# tapometer.net
KiCad netlist of a schematic drawn in EAGLE
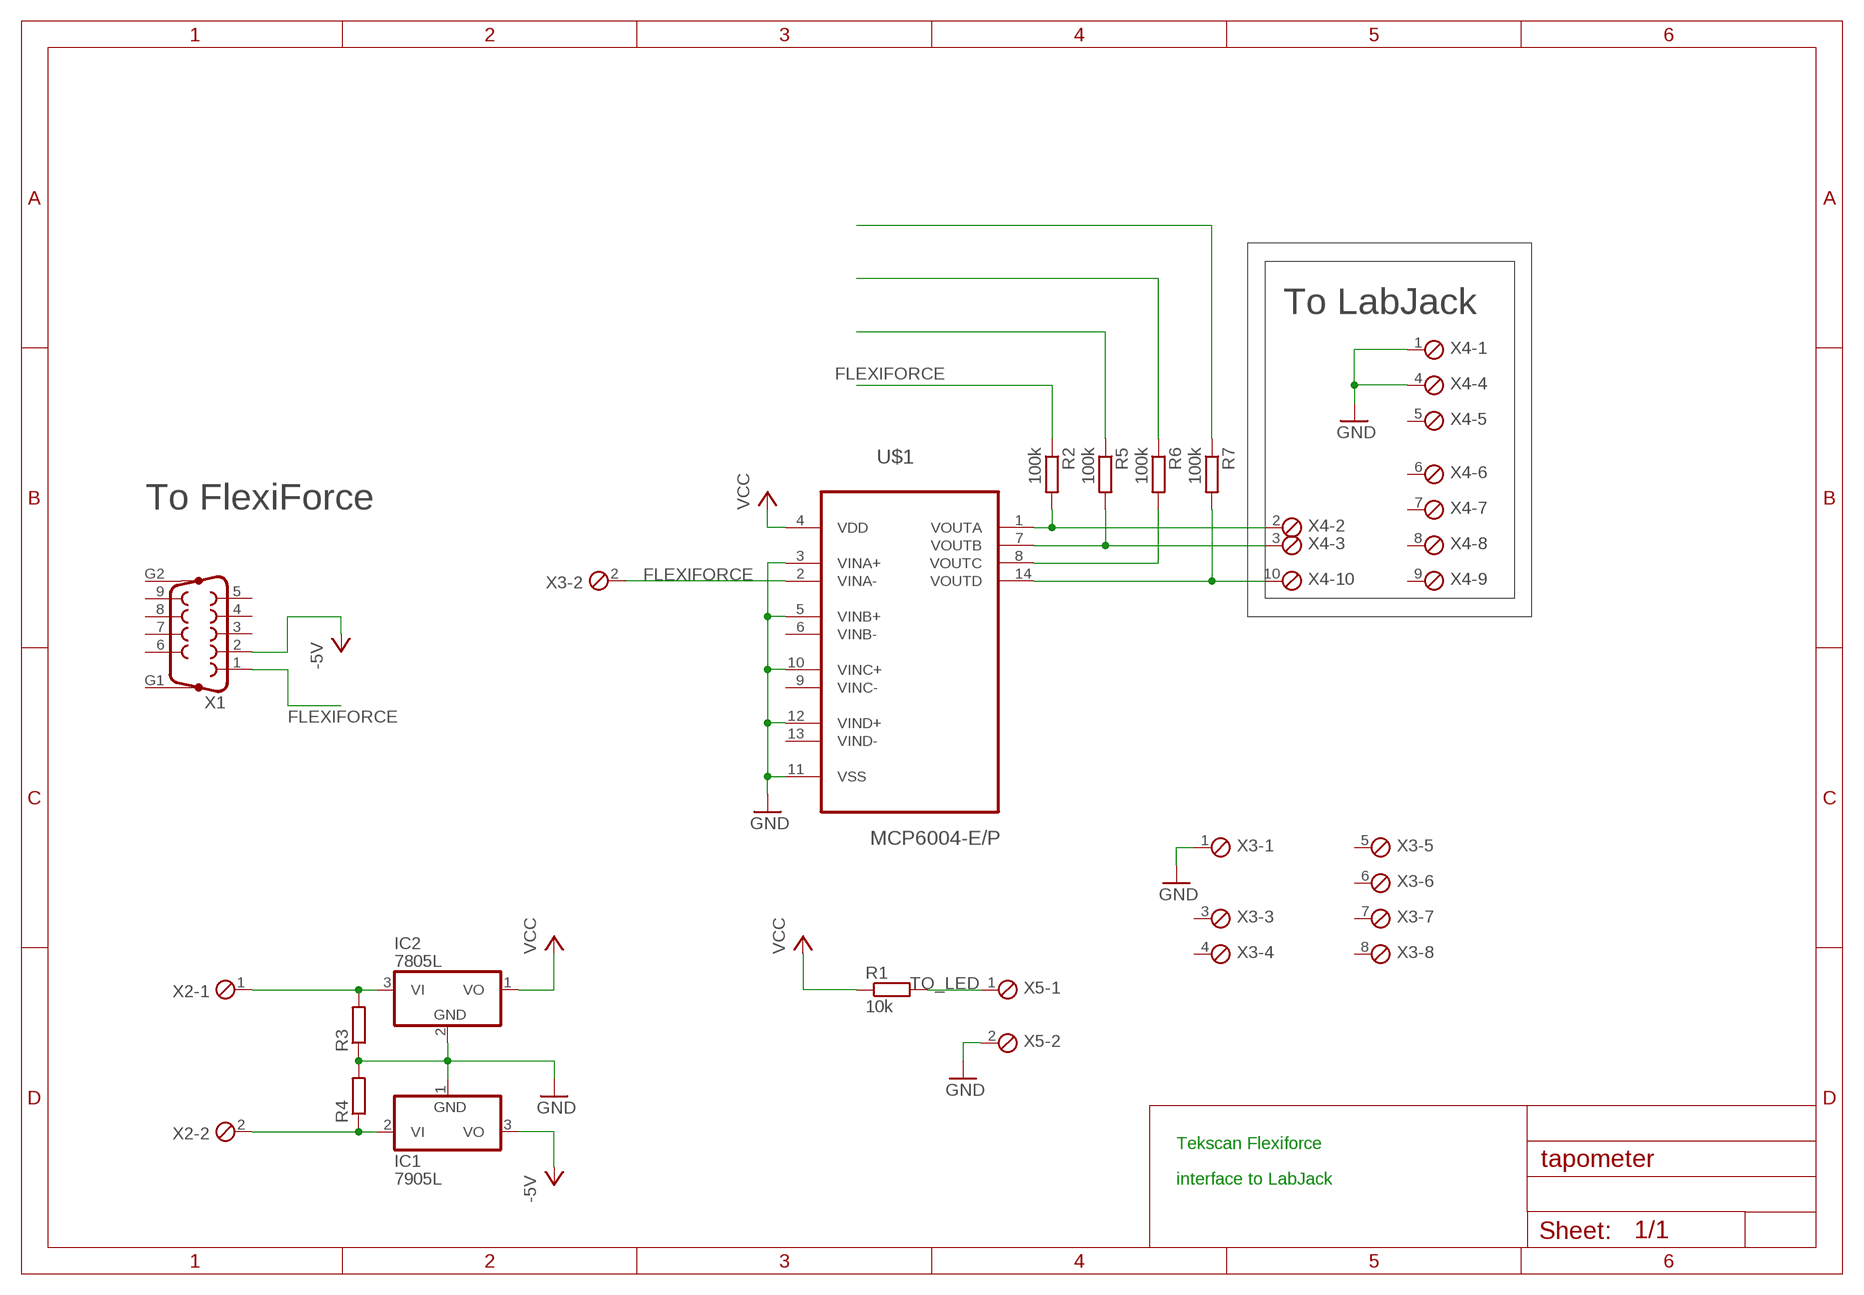
[diagram p0: schematic, sheet 1]

(export (version "E")
  (design (tool "Eeschema 10.0.6"))
  (components
    (comp (ref "IC1")
      (value "7905L")
      (footprint "eagle-import:TO92")
      (libsource (lib "eagle-import") (part "79L05"))
    )
    (comp (ref "IC2")
      (value "7805L")
      (footprint "eagle-import:TO92")
      (libsource (lib "eagle-import") (part "78L05"))
    )
    (comp (ref "R1")
      (value "10k")
      (footprint "eagle-import:0207_10")
      (libsource (lib "eagle-import") (part "R-EU_0207/10"))
    )
    (comp (ref "R2")
      (value "100k")
      (footprint "eagle-import:0207_10")
      (libsource (lib "eagle-import") (part "R-EU_0207/10"))
    )
    (comp (ref "R3")
      (value "R-EU_0207/10")
      (footprint "eagle-import:0207_10")
      (libsource (lib "eagle-import") (part "R-EU_0207/10"))
    )
    (comp (ref "R4")
      (value "R-EU_0207/10")
      (footprint "eagle-import:0207_10")
      (libsource (lib "eagle-import") (part "R-EU_0207/10"))
    )
    (comp (ref "R5")
      (value "100k")
      (footprint "eagle-import:0207_10")
      (libsource (lib "eagle-import") (part "R-EU_0207/10"))
    )
    (comp (ref "R6")
      (value "100k")
      (footprint "eagle-import:0207_10")
      (libsource (lib "eagle-import") (part "R-EU_0207/10"))
    )
    (comp (ref "R7")
      (value "100k")
      (footprint "eagle-import:0207_10")
      (libsource (lib "eagle-import") (part "R-EU_0207/10"))
    )
    (comp (ref "U$1")
      (value "MCP6004-E/P")
      (footprint "eagle-import:DIP254P762X533-14")
      (libsource (lib "eagle-import") (part "MCP6004-E/P"))
    )
    (comp (ref "X1")
      (value "F09HP")
      (footprint "eagle-import:F09HP")
      (libsource (lib "eagle-import") (part "F09HP"))
    )
    (comp (ref "X2")
      (value "MPT2")
      (footprint "eagle-import:2POL254")
      (libsource (lib "eagle-import") (part "MPT2"))
    )
    (comp (ref "X3")
      (value "MPT8")
      (footprint "eagle-import:8POL254")
      (libsource (lib "eagle-import") (part "MPT8"))
    )
    (comp (ref "X4")
      (value "MPT10")
      (footprint "eagle-import:10POL254")
      (libsource (lib "eagle-import") (part "MPT10"))
    )
    (comp (ref "X5")
      (value "MPT2")
      (footprint "eagle-import:2POL254")
      (libsource (lib "eagle-import") (part "MPT2"))
    )
  )
  (nets
    (net (code "1") (name "-5V") (class "Default")
      (node (ref "IC1") (pin "3") (pinfunction "VO_3") (pintype "passive"))
      (node (ref "X1") (pin "2") (pinfunction "2_2") (pintype "passive"))
    )
    (net (code "2") (name "/FLEXIFORCE") (class "Default")
      (node (ref "R2") (pin "1") (pinfunction "1_1") (pintype "passive"))
      (node (ref "U$1") (pin "2") (pinfunction "VINA-_2") (pintype "input"))
      (node (ref "X1") (pin "1") (pinfunction "1_1") (pintype "passive"))
      (node (ref "X3") (pin "2") (pinfunction "1_2") (pintype "passive"))
    )
    (net (code "3") (name "/TO_LED") (class "Default")
      (node (ref "R1") (pin "2") (pinfunction "2_2") (pintype "passive"))
      (node (ref "X5") (pin "1") (pinfunction "1_1") (pintype "passive"))
    )
    (net (code "4") (name "GND") (class "Default")
      (node (ref "IC1") (pin "1") (pinfunction "GND_1") (pintype "passive"))
      (node (ref "IC2") (pin "2") (pinfunction "GND_2") (pintype "passive"))
      (node (ref "R3") (pin "1") (pinfunction "1_1") (pintype "passive"))
      (node (ref "R4") (pin "2") (pinfunction "2_2") (pintype "passive"))
      (node (ref "U$1") (pin "10") (pinfunction "VINC+_10") (pintype "input"))
      (node (ref "U$1") (pin "11") (pinfunction "VSS_11") (pintype "power_in"))
      (node (ref "U$1") (pin "12") (pinfunction "VIND+_12") (pintype "input"))
      (node (ref "U$1") (pin "3") (pinfunction "VINA+_3") (pintype "input"))
      (node (ref "U$1") (pin "5") (pinfunction "VINB+_5") (pintype "input"))
      (node (ref "X3") (pin "1") (pinfunction "1_1") (pintype "passive"))
      (node (ref "X4") (pin "1") (pinfunction "1_1") (pintype "passive"))
      (node (ref "X4") (pin "4") (pinfunction "1_4") (pintype "passive"))
      (node (ref "X5") (pin "2") (pinfunction "1_2") (pintype "passive"))
    )
    (net (code "5") (name "Net-(IC1-VI)") (class "Default")
      (node (ref "IC1") (pin "2") (pinfunction "VI_2") (pintype "input"))
      (node (ref "R4") (pin "1") (pinfunction "1_1") (pintype "passive"))
      (node (ref "X2") (pin "2") (pinfunction "1_2") (pintype "passive"))
    )
    (net (code "6") (name "Net-(IC2-VI)") (class "Default")
      (node (ref "IC2") (pin "3") (pinfunction "VI_3") (pintype "input"))
      (node (ref "R3") (pin "2") (pinfunction "2_2") (pintype "passive"))
      (node (ref "X2") (pin "1") (pinfunction "1_1") (pintype "passive"))
    )
    (net (code "7") (name "Net-(U$1-VOUTA)") (class "Default")
      (node (ref "R2") (pin "2") (pinfunction "2_2") (pintype "passive"))
      (node (ref "U$1") (pin "1") (pinfunction "VOUTA_1") (pintype "output"))
      (node (ref "X4") (pin "2") (pinfunction "1_2") (pintype "passive"))
    )
    (net (code "8") (name "Net-(U$1-VOUTB)") (class "Default")
      (node (ref "R5") (pin "2") (pinfunction "2_2") (pintype "passive"))
      (node (ref "U$1") (pin "7") (pinfunction "VOUTB_7") (pintype "output"))
      (node (ref "X4") (pin "3") (pinfunction "1_3") (pintype "passive"))
    )
    (net (code "9") (name "Net-(U$1-VOUTC)") (class "Default")
      (node (ref "R6") (pin "2") (pinfunction "2_2") (pintype "passive"))
      (node (ref "U$1") (pin "8") (pinfunction "VOUTC_8") (pintype "output"))
    )
    (net (code "10") (name "Net-(U$1-VOUTD)") (class "Default")
      (node (ref "R7") (pin "2") (pinfunction "2_2") (pintype "passive"))
      (node (ref "U$1") (pin "14") (pinfunction "VOUTD_14") (pintype "output"))
      (node (ref "X4") (pin "10") (pinfunction "1_10") (pintype "passive"))
    )
    (net (code "11") (name "VCC") (class "Default")
      (node (ref "IC2") (pin "1") (pinfunction "VO_1") (pintype "passive"))
      (node (ref "R1") (pin "1") (pinfunction "1_1") (pintype "passive"))
      (node (ref "U$1") (pin "4") (pinfunction "VDD_4") (pintype "power_in"))
    )
    (net (code "12") (name "unconnected-(R5-Pad1)") (class "Default")
      (node (ref "R5") (pin "1") (pinfunction "1_1") (pintype "passive"))
    )
    (net (code "13") (name "unconnected-(R6-Pad1)") (class "Default")
      (node (ref "R6") (pin "1") (pinfunction "1_1") (pintype "passive"))
    )
    (net (code "14") (name "unconnected-(R7-Pad1)") (class "Default")
      (node (ref "R7") (pin "1") (pinfunction "1_1") (pintype "passive"))
    )
    (net (code "15") (name "unconnected-(U$1-VINB--Pad6)") (class "Default")
      (node (ref "U$1") (pin "6") (pinfunction "VINB-_6") (pintype "input"))
    )
    (net (code "16") (name "unconnected-(U$1-VINC--Pad9)") (class "Default")
      (node (ref "U$1") (pin "9") (pinfunction "VINC-_9") (pintype "input"))
    )
    (net (code "17") (name "unconnected-(U$1-VIND--Pad13)") (class "Default")
      (node (ref "U$1") (pin "13") (pinfunction "VIND-_13") (pintype "input"))
    )
    (net (code "18") (name "unconnected-(X1-Pad3)") (class "Default")
      (node (ref "X1") (pin "3") (pinfunction "3_3") (pintype "passive"))
    )
    (net (code "19") (name "unconnected-(X1-Pad4)") (class "Default")
      (node (ref "X1") (pin "4") (pinfunction "4_4") (pintype "passive"))
    )
    (net (code "20") (name "unconnected-(X1-Pad5)") (class "Default")
      (node (ref "X1") (pin "5") (pinfunction "5_5") (pintype "passive"))
    )
    (net (code "21") (name "unconnected-(X1-Pad6)") (class "Default")
      (node (ref "X1") (pin "6") (pinfunction "6_6") (pintype "passive"))
    )
    (net (code "22") (name "unconnected-(X1-Pad7)") (class "Default")
      (node (ref "X1") (pin "7") (pinfunction "7_7") (pintype "passive"))
    )
    (net (code "23") (name "unconnected-(X1-Pad8)") (class "Default")
      (node (ref "X1") (pin "8") (pinfunction "8_8") (pintype "passive"))
    )
    (net (code "24") (name "unconnected-(X1-Pad9)") (class "Default")
      (node (ref "X1") (pin "9") (pinfunction "9_9") (pintype "passive"))
    )
    (net (code "25") (name "unconnected-(X1-PadG1)") (class "Default")
      (node (ref "X1") (pin "G1") (pinfunction "G1_G1") (pintype "passive"))
    )
    (net (code "26") (name "unconnected-(X1-PadG2)") (class "Default")
      (node (ref "X1") (pin "G2") (pinfunction "G2_G2") (pintype "passive"))
    )
    (net (code "27") (name "unconnected-(X3C-1-Pad3)") (class "Default")
      (node (ref "X3") (pin "3") (pinfunction "1_3") (pintype "passive"))
    )
    (net (code "28") (name "unconnected-(X3D-1-Pad4)") (class "Default")
      (node (ref "X3") (pin "4") (pinfunction "1_4") (pintype "passive"))
    )
    (net (code "29") (name "unconnected-(X3E-1-Pad5)") (class "Default")
      (node (ref "X3") (pin "5") (pinfunction "1_5") (pintype "passive"))
    )
    (net (code "30") (name "unconnected-(X3F-1-Pad6)") (class "Default")
      (node (ref "X3") (pin "6") (pinfunction "1_6") (pintype "passive"))
    )
    (net (code "31") (name "unconnected-(X3G-1-Pad7)") (class "Default")
      (node (ref "X3") (pin "7") (pinfunction "1_7") (pintype "passive"))
    )
    (net (code "32") (name "unconnected-(X3H-1-Pad8)") (class "Default")
      (node (ref "X3") (pin "8") (pinfunction "1_8") (pintype "passive"))
    )
    (net (code "33") (name "unconnected-(X4F-1-Pad5)") (class "Default")
      (node (ref "X4") (pin "5") (pinfunction "1_5") (pintype "passive"))
    )
    (net (code "34") (name "unconnected-(X4G-1-Pad6)") (class "Default")
      (node (ref "X4") (pin "6") (pinfunction "1_6") (pintype "passive"))
    )
    (net (code "35") (name "unconnected-(X4H-1-Pad7)") (class "Default")
      (node (ref "X4") (pin "7") (pinfunction "1_7") (pintype "passive"))
    )
    (net (code "36") (name "unconnected-(X4I-1-Pad8)") (class "Default")
      (node (ref "X4") (pin "8") (pinfunction "1_8") (pintype "passive"))
    )
    (net (code "37") (name "unconnected-(X4J-1-Pad9)") (class "Default")
      (node (ref "X4") (pin "9") (pinfunction "1_9") (pintype "passive"))
    )
  )
)
